# Adafruit_Si471x_PCB.net
KiCad netlist of a schematic drawn in EAGLE
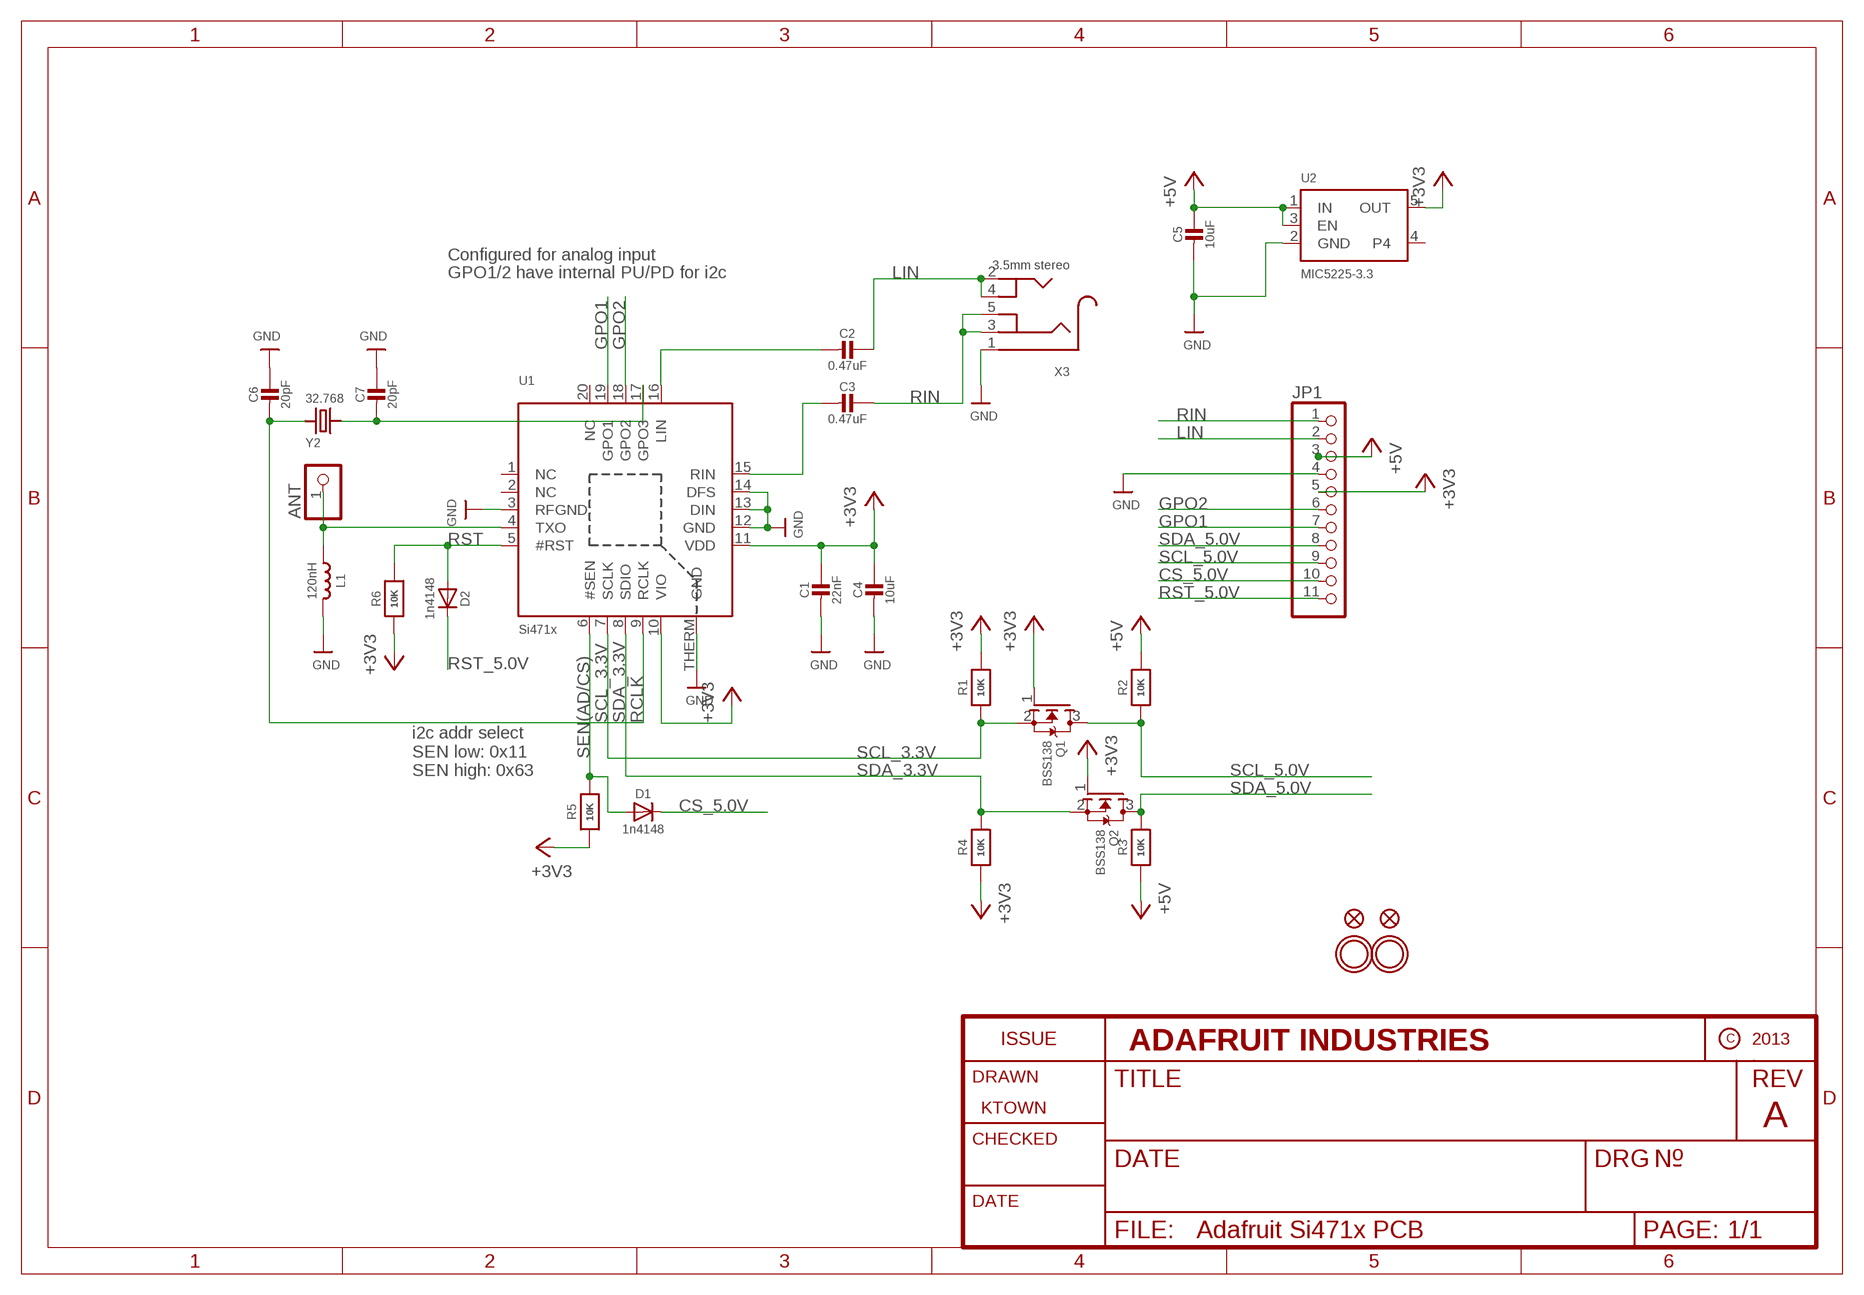
[diagram p0: schematic, sheet 1]

(export (version "E")
  (design (tool "Eeschema 10.0.6"))
  (components
    (comp (ref "ANT")
      (value "PINHD-1X1")
      (footprint "eagle-import:1X01")
      (libsource (lib "eagle-import") (part "PINHD-1X1"))
    )
    (comp (ref "C1")
      (value "22nF")
      (footprint "eagle-import:0805-NO")
      (libsource (lib "eagle-import") (part "CAP_CERAMIC0805-NOOUTLINE"))
    )
    (comp (ref "C2")
      (value "0.47uF")
      (footprint "eagle-import:0805-NO")
      (libsource (lib "eagle-import") (part "CAP_CERAMIC0805-NOOUTLINE"))
    )
    (comp (ref "C3")
      (value "0.47uF")
      (footprint "eagle-import:0805-NO")
      (libsource (lib "eagle-import") (part "CAP_CERAMIC0805-NOOUTLINE"))
    )
    (comp (ref "C4")
      (value "10uF")
      (footprint "eagle-import:0805-NO")
      (libsource (lib "eagle-import") (part "CAP_CERAMIC0805-NOOUTLINE"))
    )
    (comp (ref "C5")
      (value "10uF")
      (footprint "eagle-import:0805-NO")
      (libsource (lib "eagle-import") (part "CAP_CERAMIC0805-NOOUTLINE"))
    )
    (comp (ref "C6")
      (value "20pF")
      (footprint "eagle-import:0805-NO")
      (libsource (lib "eagle-import") (part "CAP_CERAMIC0805-NOOUTLINE"))
    )
    (comp (ref "C7")
      (value "20pF")
      (footprint "eagle-import:0805-NO")
      (libsource (lib "eagle-import") (part "CAP_CERAMIC0805-NOOUTLINE"))
    )
    (comp (ref "D1")
      (value "1n4148")
      (footprint "eagle-import:SOD-323")
      (libsource (lib "eagle-import") (part "DIODESOD-323"))
    )
    (comp (ref "D2")
      (value "1n4148")
      (footprint "eagle-import:SOD-323")
      (libsource (lib "eagle-import") (part "DIODESOD-323"))
    )
    (comp (ref "FID1")
      (value "FIDUCIAL\"\"")
      (footprint "eagle-import:FIDUCIAL_1MM")
      (libsource (lib "eagle-import") (part "FIDUCIAL{dblquote}{dblquote}"))
    )
    (comp (ref "FID2")
      (value "FIDUCIAL\"\"")
      (footprint "eagle-import:FIDUCIAL_1MM")
      (libsource (lib "eagle-import") (part "FIDUCIAL{dblquote}{dblquote}"))
    )
    (comp (ref "JP1")
      (value "HEADER-1X11")
      (footprint "eagle-import:1X11_ROUND")
      (libsource (lib "eagle-import") (part "HEADER-1X11"))
    )
    (comp (ref "L1")
      (value "120nH")
      (footprint "eagle-import:_0805")
      (libsource (lib "eagle-import") (part "INDUCTOR_0805"))
    )
    (comp (ref "Q1")
      (value "BSS138")
      (footprint "eagle-import:SOT23")
      (libsource (lib "eagle-import") (part "MOSFET-NREFLOW"))
    )
    (comp (ref "Q2")
      (value "BSS138")
      (footprint "eagle-import:SOT23")
      (libsource (lib "eagle-import") (part "MOSFET-NREFLOW"))
    )
    (comp (ref "R1")
      (value "10K")
      (footprint "eagle-import:0805-NO")
      (libsource (lib "eagle-import") (part "RESISTOR0805_NOOUTLINE"))
    )
    (comp (ref "R2")
      (value "10K")
      (footprint "eagle-import:_0805MP")
      (libsource (lib "eagle-import") (part "RESISTOR_0805MP"))
    )
    (comp (ref "R3")
      (value "10K")
      (footprint "eagle-import:0805-NO")
      (libsource (lib "eagle-import") (part "RESISTOR0805_NOOUTLINE"))
    )
    (comp (ref "R4")
      (value "10K")
      (footprint "eagle-import:_0805MP")
      (libsource (lib "eagle-import") (part "RESISTOR_0805MP"))
    )
    (comp (ref "R5")
      (value "10K")
      (footprint "eagle-import:0805-NO")
      (libsource (lib "eagle-import") (part "RESISTOR0805_NOOUTLINE"))
    )
    (comp (ref "R6")
      (value "10K")
      (footprint "eagle-import:0805-NO")
      (libsource (lib "eagle-import") (part "RESISTOR0805_NOOUTLINE"))
    )
    (comp (ref "U$15")
      (value "MOUNTINGHOLE2.5")
      (footprint "eagle-import:MOUNTINGHOLE_2.5_PLATED")
      (libsource (lib "eagle-import") (part "MOUNTINGHOLE2.5"))
    )
    (comp (ref "U$17")
      (value "MOUNTINGHOLE2.5")
      (footprint "eagle-import:MOUNTINGHOLE_2.5_PLATED")
      (libsource (lib "eagle-import") (part "MOUNTINGHOLE2.5"))
    )
    (comp (ref "U1")
      (value "Si471x")
      (footprint "eagle-import:SI471X")
      (libsource (lib "eagle-import") (part "SI471X"))
    )
    (comp (ref "U2")
      (value "MIC5225-3.3")
      (footprint "eagle-import:SOT23-5")
      (libsource (lib "eagle-import") (part "VREG_SOT23-5"))
    )
    (comp (ref "X3")
      (value "3.5mm stereo")
      (footprint "eagle-import:4UCONN_19269")
      (libsource (lib "eagle-import") (part "AUDIO_3.5MMJACK"))
    )
    (comp (ref "Y2")
      (value "32.768")
      (footprint "eagle-import:CRYSTAL_8X3.8")
      (libsource (lib "eagle-import") (part "CRYSTAL8.0X3.8"))
    )
  )
  (nets
    (net (code "1") (name "+3V3") (class "Default")
      (node (ref "C1") (pin "1") (pinfunction "1_1") (pintype "passive"))
      (node (ref "C4") (pin "1") (pinfunction "1_1") (pintype "passive"))
      (node (ref "JP1") (pin "5") (pinfunction "5_5") (pintype "passive"))
      (node (ref "Q1") (pin "1") (pinfunction "G_1") (pintype "bidirectional"))
      (node (ref "Q2") (pin "1") (pinfunction "G_1") (pintype "bidirectional"))
      (node (ref "R1") (pin "2") (pinfunction "2_2") (pintype "passive"))
      (node (ref "R4") (pin "1") (pinfunction "1_1") (pintype "passive"))
      (node (ref "R5") (pin "1") (pinfunction "1_1") (pintype "passive"))
      (node (ref "R6") (pin "1") (pinfunction "1_1") (pintype "passive"))
      (node (ref "U1") (pin "10") (pinfunction "VIO_10") (pintype "bidirectional"))
      (node (ref "U1") (pin "11") (pinfunction "VDD_11") (pintype "bidirectional"))
      (node (ref "U2") (pin "5") (pinfunction "OUT_5") (pintype "power_in"))
    )
    (net (code "2") (name "+5V") (class "Default")
      (node (ref "C5") (pin "1") (pinfunction "1_1") (pintype "passive"))
      (node (ref "JP1") (pin "3") (pinfunction "3_3") (pintype "passive"))
      (node (ref "R2") (pin "2") (pinfunction "2_2") (pintype "passive"))
      (node (ref "R3") (pin "1") (pinfunction "1_1") (pintype "passive"))
      (node (ref "U2") (pin "1") (pinfunction "IN_1") (pintype "power_in"))
      (node (ref "U2") (pin "3") (pinfunction "EN_3") (pintype "input"))
    )
    (net (code "3") (name "/CS_5.0V") (class "Default")
      (node (ref "D1") (pin "C") (pinfunction "C_C") (pintype "passive"))
      (node (ref "JP1") (pin "10") (pinfunction "10_10") (pintype "passive"))
    )
    (net (code "4") (name "/GPO1") (class "Default")
      (node (ref "JP1") (pin "7") (pinfunction "7_7") (pintype "passive"))
      (node (ref "U1") (pin "19") (pinfunction "GPO1_19") (pintype "bidirectional"))
    )
    (net (code "5") (name "/GPO2") (class "Default")
      (node (ref "JP1") (pin "6") (pinfunction "6_6") (pintype "passive"))
      (node (ref "U1") (pin "18") (pinfunction "GPO2_18") (pintype "bidirectional"))
    )
    (net (code "6") (name "/LIN") (class "Default")
      (node (ref "C2") (pin "1") (pinfunction "1_1") (pintype "passive"))
      (node (ref "JP1") (pin "2") (pinfunction "2_2") (pintype "passive"))
      (node (ref "X3") (pin "2") (pinfunction "P$5_2") (pintype "bidirectional"))
      (node (ref "X3") (pin "4") (pinfunction "P$4_4") (pintype "bidirectional"))
    )
    (net (code "7") (name "/RCLK") (class "Default")
      (node (ref "C6") (pin "2") (pinfunction "2_2") (pintype "passive"))
      (node (ref "U1") (pin "9") (pinfunction "RCLK_9") (pintype "bidirectional"))
      (node (ref "Y2") (pin "P$1") (pinfunction "1_P$1") (pintype "passive"))
    )
    (net (code "8") (name "/RIN") (class "Default")
      (node (ref "C3") (pin "1") (pinfunction "1_1") (pintype "passive"))
      (node (ref "JP1") (pin "1") (pinfunction "1_1") (pintype "passive"))
      (node (ref "X3") (pin "3") (pinfunction "P$2_3") (pintype "bidirectional"))
      (node (ref "X3") (pin "5") (pinfunction "P$3_5") (pintype "bidirectional"))
    )
    (net (code "9") (name "/RST") (class "Default")
      (node (ref "D2") (pin "A") (pinfunction "A_A") (pintype "passive"))
      (node (ref "R6") (pin "2") (pinfunction "2_2") (pintype "passive"))
      (node (ref "U1") (pin "5") (pinfunction "#RST_5") (pintype "bidirectional"))
    )
    (net (code "10") (name "/RST_5.0V") (class "Default")
      (node (ref "D2") (pin "C") (pinfunction "C_C") (pintype "passive"))
      (node (ref "JP1") (pin "11") (pinfunction "11_11") (pintype "passive"))
    )
    (net (code "11") (name "/SCL_3.3V") (class "Default")
      (node (ref "Q1") (pin "2") (pinfunction "S_2") (pintype "bidirectional"))
      (node (ref "R1") (pin "1") (pinfunction "1_1") (pintype "passive"))
      (node (ref "U1") (pin "7") (pinfunction "SCLK_7") (pintype "bidirectional"))
    )
    (net (code "12") (name "/SCL_5.0V") (class "Default")
      (node (ref "JP1") (pin "9") (pinfunction "9_9") (pintype "passive"))
      (node (ref "Q1") (pin "3") (pinfunction "D_3") (pintype "bidirectional"))
      (node (ref "R2") (pin "1") (pinfunction "1_1") (pintype "passive"))
    )
    (net (code "13") (name "/SDA_3.3V") (class "Default")
      (node (ref "Q2") (pin "2") (pinfunction "S_2") (pintype "bidirectional"))
      (node (ref "R4") (pin "2") (pinfunction "2_2") (pintype "passive"))
      (node (ref "U1") (pin "8") (pinfunction "SDIO_8") (pintype "bidirectional"))
    )
    (net (code "14") (name "/SDA_5.0V") (class "Default")
      (node (ref "JP1") (pin "8") (pinfunction "8_8") (pintype "passive"))
      (node (ref "Q2") (pin "3") (pinfunction "D_3") (pintype "bidirectional"))
      (node (ref "R3") (pin "2") (pinfunction "2_2") (pintype "passive"))
    )
    (net (code "15") (name "/SEN(AD{slash}CS)") (class "Default")
      (node (ref "D1") (pin "A") (pinfunction "A_A") (pintype "passive"))
      (node (ref "R5") (pin "2") (pinfunction "2_2") (pintype "passive"))
      (node (ref "U1") (pin "6") (pinfunction "#SEN_6") (pintype "bidirectional"))
    )
    (net (code "16") (name "GND") (class "Default")
      (node (ref "C1") (pin "2") (pinfunction "2_2") (pintype "passive"))
      (node (ref "C4") (pin "2") (pinfunction "2_2") (pintype "passive"))
      (node (ref "C5") (pin "2") (pinfunction "2_2") (pintype "passive"))
      (node (ref "C6") (pin "1") (pinfunction "1_1") (pintype "passive"))
      (node (ref "C7") (pin "1") (pinfunction "1_1") (pintype "passive"))
      (node (ref "JP1") (pin "4") (pinfunction "4_4") (pintype "passive"))
      (node (ref "L1") (pin "2") (pinfunction "2_2") (pintype "passive"))
      (node (ref "U1") (pin "12") (pinfunction "GND_12") (pintype "bidirectional"))
      (node (ref "U1") (pin "13") (pinfunction "DIN_13") (pintype "bidirectional"))
      (node (ref "U1") (pin "14") (pinfunction "DFS_14") (pintype "bidirectional"))
      (node (ref "U1") (pin "3") (pinfunction "RFGND_3") (pintype "bidirectional"))
      (node (ref "U1") (pin "THERM") (pinfunction "GND_THERM") (pintype "bidirectional"))
      (node (ref "U2") (pin "2") (pinfunction "GND_2") (pintype "power_in"))
      (node (ref "X3") (pin "1") (pinfunction "P$1_1") (pintype "bidirectional"))
    )
    (net (code "17") (name "Net-(U1-GPO3)") (class "Default")
      (node (ref "C7") (pin "2") (pinfunction "2_2") (pintype "passive"))
      (node (ref "U1") (pin "17") (pinfunction "GPO3_17") (pintype "bidirectional"))
      (node (ref "Y2") (pin "P$4") (pinfunction "2_P$4") (pintype "passive"))
    )
    (net (code "18") (name "Net-(U1-LIN)") (class "Default")
      (node (ref "C2") (pin "2") (pinfunction "2_2") (pintype "passive"))
      (node (ref "U1") (pin "16") (pinfunction "LIN_16") (pintype "bidirectional"))
    )
    (net (code "19") (name "Net-(U1-RIN)") (class "Default")
      (node (ref "C3") (pin "2") (pinfunction "2_2") (pintype "passive"))
      (node (ref "U1") (pin "15") (pinfunction "RIN_15") (pintype "bidirectional"))
    )
    (net (code "20") (name "Net-(U1-TXO)") (class "Default")
      (node (ref "ANT") (pin "1") (pinfunction "1_1") (pintype "passive"))
      (node (ref "L1") (pin "1") (pinfunction "1_1") (pintype "passive"))
      (node (ref "U1") (pin "4") (pinfunction "TXO_4") (pintype "bidirectional"))
    )
    (net (code "21") (name "unconnected-(U1-NC-Pad1)") (class "Default")
      (node (ref "U1") (pin "1") (pinfunction "NC_1") (pintype "bidirectional"))
    )
    (net (code "22") (name "unconnected-(U1-NC-Pad2)") (class "Default")
      (node (ref "U1") (pin "2") (pinfunction "NC_2") (pintype "bidirectional"))
    )
    (net (code "23") (name "unconnected-(U1-NC-Pad20)") (class "Default")
      (node (ref "U1") (pin "20") (pinfunction "NC_20") (pintype "bidirectional"))
    )
    (net (code "24") (name "unconnected-(U2-P4-Pad4)") (class "Default")
      (node (ref "U2") (pin "4") (pinfunction "P4_4") (pintype "bidirectional"))
    )
  )
)
